# SONAR_UPDATEDSCH.net
KiCad netlist of a schematic drawn in EAGLE
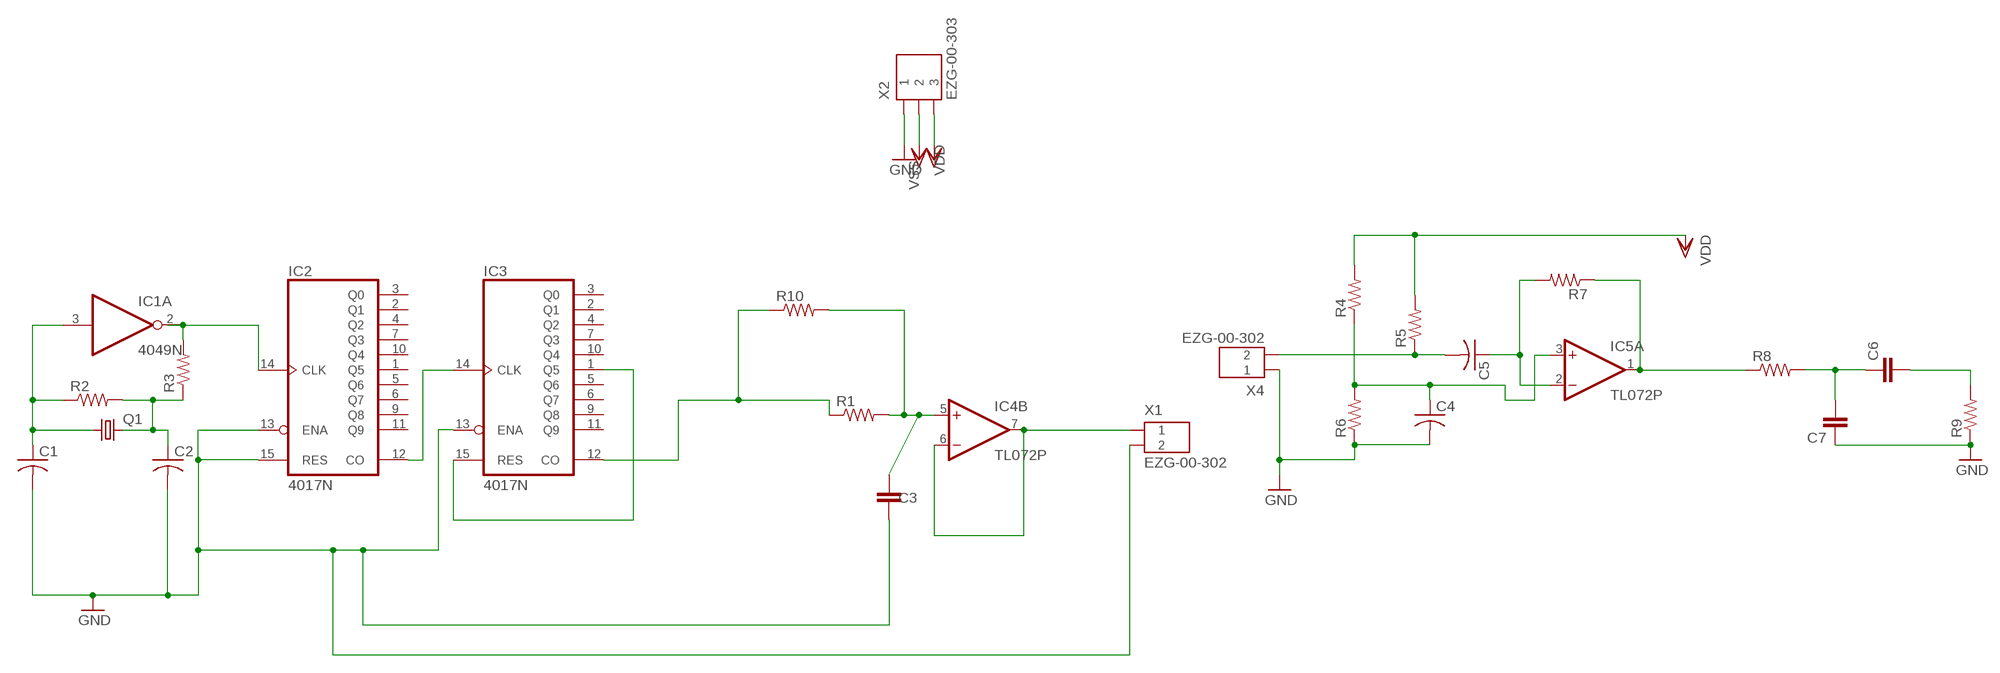
[diagram p0: schematic, sheet 1]

(export (version "E")
  (design (tool "Eeschema 10.0.6"))
  (components
    (comp (ref "C1")
      (value "C-US050-025X075")
      (footprint "eagle-import:C050-025X075")
      (libsource (lib "eagle-import") (part "C-US050-025X075"))
    )
    (comp (ref "C2")
      (value "C-US050-025X075")
      (footprint "eagle-import:C050-025X075")
      (libsource (lib "eagle-import") (part "C-US050-025X075"))
    )
    (comp (ref "C3")
      (value "C2.5/2")
      (footprint "eagle-import:C2.5-2")
      (libsource (lib "eagle-import") (part "C2.5/2"))
    )
    (comp (ref "C4")
      (value "C-US025-030X050")
      (footprint "eagle-import:C025-030X050")
      (libsource (lib "eagle-import") (part "C-US025-030X050"))
    )
    (comp (ref "C5")
      (value "C-US025-030X050")
      (footprint "eagle-import:C025-030X050")
      (libsource (lib "eagle-import") (part "C-US025-030X050"))
    )
    (comp (ref "C6")
      (value "C-EU025-030X050")
      (footprint "eagle-import:C025-030X050")
      (libsource (lib "eagle-import") (part "C-EU025-030X050"))
    )
    (comp (ref "C7")
      (value "C-EU025-030X050")
      (footprint "eagle-import:C025-030X050")
      (libsource (lib "eagle-import") (part "C-EU025-030X050"))
    )
    (comp (ref "IC1")
      (value "4049N")
      (footprint "eagle-import:DIL16")
      (libsource (lib "eagle-import") (part "4049N"))
    )
    (comp (ref "IC2")
      (value "4017N")
      (footprint "eagle-import:DIL16")
      (libsource (lib "eagle-import") (part "4017N"))
    )
    (comp (ref "IC3")
      (value "4017N")
      (footprint "eagle-import:DIL16")
      (libsource (lib "eagle-import") (part "4017N"))
    )
    (comp (ref "IC4")
      (value "TL072P")
      (footprint "eagle-import:DIL08")
      (libsource (lib "eagle-import") (part "TL072P"))
    )
    (comp (ref "IC5")
      (value "TL072P")
      (footprint "eagle-import:DIL08")
      (libsource (lib "eagle-import") (part "TL072P"))
    )
    (comp (ref "Q1")
      (value "CRYSTALHC49U-V")
      (footprint "eagle-import:HC49U-V")
      (libsource (lib "eagle-import") (part "CRYSTALHC49U-V"))
    )
    (comp (ref "R1")
      (value "R-US_0207/10")
      (footprint "eagle-import:0207_10")
      (libsource (lib "eagle-import") (part "R-US_0207/10"))
    )
    (comp (ref "R2")
      (value "R-US_0207/10")
      (footprint "eagle-import:0207_10")
      (libsource (lib "eagle-import") (part "R-US_0207/10"))
    )
    (comp (ref "R3")
      (value "R-US_0207/10")
      (footprint "eagle-import:0207_10")
      (libsource (lib "eagle-import") (part "R-US_0207/10"))
    )
    (comp (ref "R4")
      (value "R-US_0207/7")
      (footprint "eagle-import:0207_7")
      (libsource (lib "eagle-import") (part "R-US_0207/7"))
    )
    (comp (ref "R5")
      (value "R-US_0207/7")
      (footprint "eagle-import:0207_7")
      (libsource (lib "eagle-import") (part "R-US_0207/7"))
    )
    (comp (ref "R6")
      (value "R-US_0207/7")
      (footprint "eagle-import:0207_7")
      (libsource (lib "eagle-import") (part "R-US_0207/7"))
    )
    (comp (ref "R7")
      (value "R-US_0207/7")
      (footprint "eagle-import:0207_7")
      (libsource (lib "eagle-import") (part "R-US_0207/7"))
    )
    (comp (ref "R8")
      (value "R-US_0207/10")
      (footprint "eagle-import:0207_10")
      (libsource (lib "eagle-import") (part "R-US_0207/10"))
    )
    (comp (ref "R9")
      (value "R-US_0207/10")
      (footprint "eagle-import:0207_10")
      (libsource (lib "eagle-import") (part "R-US_0207/10"))
    )
    (comp (ref "R10")
      (value "R-US_0207/7")
      (footprint "eagle-import:0207_7")
      (libsource (lib "eagle-import") (part "R-US_0207/7"))
    )
    (comp (ref "X1")
      (value "EZG-00-302")
      (footprint "eagle-import:EZG-00-302")
      (libsource (lib "eagle-import") (part "EZG-?-30200"))
    )
    (comp (ref "X2")
      (value "EZG-00-303")
      (footprint "eagle-import:EZG-00-303")
      (libsource (lib "eagle-import") (part "EZG-?-30300"))
    )
    (comp (ref "X4")
      (value "EZG-00-302")
      (footprint "eagle-import:EZG-00-302")
      (libsource (lib "eagle-import") (part "EZG-?-30200"))
    )
  )
  (nets
    (net (code "1") (name "GND") (class "Default")
      (node (ref "C1") (pin "2") (pinfunction "2_2") (pintype "passive"))
      (node (ref "C2") (pin "2") (pinfunction "2_2") (pintype "passive"))
      (node (ref "C3") (pin "2") (pinfunction "2_2") (pintype "passive"))
      (node (ref "C4") (pin "2") (pinfunction "2_2") (pintype "passive"))
      (node (ref "C7") (pin "1") (pinfunction "1_1") (pintype "passive"))
      (node (ref "IC2") (pin "13") (pinfunction "ENA_13") (pintype "input"))
      (node (ref "IC2") (pin "15") (pinfunction "RES_15") (pintype "input"))
      (node (ref "IC3") (pin "13") (pinfunction "ENA_13") (pintype "input"))
      (node (ref "R6") (pin "1") (pinfunction "1_1") (pintype "passive"))
      (node (ref "R9") (pin "1") (pinfunction "1_1") (pintype "passive"))
      (node (ref "X1") (pin "2") (pinfunction "2_2") (pintype "passive"))
      (node (ref "X2") (pin "1") (pinfunction "1_1") (pintype "passive"))
      (node (ref "X4") (pin "1") (pinfunction "1_1") (pintype "passive"))
    )
    (net (code "2") (name "Net-(C2-Pad1)") (class "Default")
      (node (ref "C2") (pin "1") (pinfunction "1_1") (pintype "passive"))
      (node (ref "Q1") (pin "2") (pinfunction "2_2") (pintype "passive"))
      (node (ref "R2") (pin "2") (pinfunction "2_2") (pintype "passive"))
      (node (ref "R3") (pin "1") (pinfunction "1_1") (pintype "passive"))
    )
    (net (code "3") (name "Net-(C5-Pad2)") (class "Default")
      (node (ref "C5") (pin "2") (pinfunction "2_2") (pintype "passive"))
      (node (ref "R5") (pin "1") (pinfunction "1_1") (pintype "passive"))
      (node (ref "X4") (pin "2") (pinfunction "2_2") (pintype "passive"))
    )
    (net (code "4") (name "Net-(C6-Pad1)") (class "Default")
      (node (ref "C6") (pin "1") (pinfunction "1_1") (pintype "passive"))
      (node (ref "C7") (pin "2") (pinfunction "2_2") (pintype "passive"))
      (node (ref "R8") (pin "2") (pinfunction "2_2") (pintype "passive"))
    )
    (net (code "5") (name "Net-(C6-Pad2)") (class "Default")
      (node (ref "C6") (pin "2") (pinfunction "2_2") (pintype "passive"))
      (node (ref "R9") (pin "2") (pinfunction "2_2") (pintype "passive"))
    )
    (net (code "6") (name "Net-(IC1A-I)") (class "Default")
      (node (ref "C1") (pin "1") (pinfunction "1_1") (pintype "passive"))
      (node (ref "IC1") (pin "3") (pinfunction "I_3") (pintype "input"))
      (node (ref "Q1") (pin "1") (pinfunction "1_1") (pintype "passive"))
      (node (ref "R2") (pin "1") (pinfunction "1_1") (pintype "passive"))
    )
    (net (code "7") (name "Net-(IC1A-O)") (class "Default")
      (node (ref "IC1") (pin "2") (pinfunction "O_2") (pintype "output"))
      (node (ref "IC2") (pin "14") (pinfunction "CLK_14") (pintype "input"))
      (node (ref "R3") (pin "2") (pinfunction "2_2") (pintype "passive"))
    )
    (net (code "8") (name "Net-(IC2A-CO)") (class "Default")
      (node (ref "IC2") (pin "12") (pinfunction "CO_12") (pintype "output"))
      (node (ref "IC3") (pin "14") (pinfunction "CLK_14") (pintype "input"))
    )
    (net (code "9") (name "Net-(IC3A-CO)") (class "Default")
      (node (ref "IC3") (pin "12") (pinfunction "CO_12") (pintype "output"))
      (node (ref "R1") (pin "1") (pinfunction "1_1") (pintype "passive"))
      (node (ref "R10") (pin "1") (pinfunction "1_1") (pintype "passive"))
    )
    (net (code "10") (name "Net-(IC3A-Q5)") (class "Default")
      (node (ref "IC3") (pin "1") (pinfunction "Q5_1") (pintype "output"))
      (node (ref "IC3") (pin "15") (pinfunction "RES_15") (pintype "input"))
    )
    (net (code "11") (name "Net-(IC4B-+IN)") (class "Default")
      (node (ref "C3") (pin "1") (pinfunction "1_1") (pintype "passive"))
      (node (ref "IC4") (pin "5") (pinfunction "+IN_5") (pintype "input"))
      (node (ref "R1") (pin "2") (pinfunction "2_2") (pintype "passive"))
      (node (ref "R10") (pin "2") (pinfunction "2_2") (pintype "passive"))
    )
    (net (code "12") (name "Net-(IC4B--IN)") (class "Default")
      (node (ref "IC4") (pin "6") (pinfunction "-IN_6") (pintype "input"))
      (node (ref "IC4") (pin "7") (pinfunction "OUT_7") (pintype "output"))
      (node (ref "X1") (pin "1") (pinfunction "1_1") (pintype "passive"))
    )
    (net (code "13") (name "Net-(IC5A-+IN)") (class "Default")
      (node (ref "C4") (pin "1") (pinfunction "1_1") (pintype "passive"))
      (node (ref "IC5") (pin "3") (pinfunction "+IN_3") (pintype "input"))
      (node (ref "R4") (pin "1") (pinfunction "1_1") (pintype "passive"))
      (node (ref "R6") (pin "2") (pinfunction "2_2") (pintype "passive"))
    )
    (net (code "14") (name "Net-(IC5A--IN)") (class "Default")
      (node (ref "C5") (pin "1") (pinfunction "1_1") (pintype "passive"))
      (node (ref "IC5") (pin "2") (pinfunction "-IN_2") (pintype "input"))
      (node (ref "R7") (pin "2") (pinfunction "2_2") (pintype "passive"))
    )
    (net (code "15") (name "Net-(IC5A-OUT)") (class "Default")
      (node (ref "IC5") (pin "1") (pinfunction "OUT_1") (pintype "output"))
      (node (ref "R7") (pin "1") (pinfunction "1_1") (pintype "passive"))
      (node (ref "R8") (pin "1") (pinfunction "1_1") (pintype "passive"))
    )
    (net (code "16") (name "VDD") (class "Default")
      (node (ref "R4") (pin "2") (pinfunction "2_2") (pintype "passive"))
      (node (ref "R5") (pin "2") (pinfunction "2_2") (pintype "passive"))
      (node (ref "X2") (pin "2") (pinfunction "2_2") (pintype "passive"))
    )
    (net (code "17") (name "VSS") (class "Default")
      (node (ref "X2") (pin "3") (pinfunction "3_3") (pintype "passive"))
    )
    (net (code "18") (name "unconnected-(IC2A-Q0-Pad3)") (class "Default")
      (node (ref "IC2") (pin "3") (pinfunction "Q0_3") (pintype "output"))
    )
    (net (code "19") (name "unconnected-(IC2A-Q1-Pad2)") (class "Default")
      (node (ref "IC2") (pin "2") (pinfunction "Q1_2") (pintype "output"))
    )
    (net (code "20") (name "unconnected-(IC2A-Q2-Pad4)") (class "Default")
      (node (ref "IC2") (pin "4") (pinfunction "Q2_4") (pintype "output"))
    )
    (net (code "21") (name "unconnected-(IC2A-Q3-Pad7)") (class "Default")
      (node (ref "IC2") (pin "7") (pinfunction "Q3_7") (pintype "output"))
    )
    (net (code "22") (name "unconnected-(IC2A-Q4-Pad10)") (class "Default")
      (node (ref "IC2") (pin "10") (pinfunction "Q4_10") (pintype "output"))
    )
    (net (code "23") (name "unconnected-(IC2A-Q5-Pad1)") (class "Default")
      (node (ref "IC2") (pin "1") (pinfunction "Q5_1") (pintype "output"))
    )
    (net (code "24") (name "unconnected-(IC2A-Q6-Pad5)") (class "Default")
      (node (ref "IC2") (pin "5") (pinfunction "Q6_5") (pintype "output"))
    )
    (net (code "25") (name "unconnected-(IC2A-Q7-Pad6)") (class "Default")
      (node (ref "IC2") (pin "6") (pinfunction "Q7_6") (pintype "output"))
    )
    (net (code "26") (name "unconnected-(IC2A-Q8-Pad9)") (class "Default")
      (node (ref "IC2") (pin "9") (pinfunction "Q8_9") (pintype "output"))
    )
    (net (code "27") (name "unconnected-(IC2A-Q9-Pad11)") (class "Default")
      (node (ref "IC2") (pin "11") (pinfunction "Q9_11") (pintype "output"))
    )
    (net (code "28") (name "unconnected-(IC3A-Q0-Pad3)") (class "Default")
      (node (ref "IC3") (pin "3") (pinfunction "Q0_3") (pintype "output"))
    )
    (net (code "29") (name "unconnected-(IC3A-Q1-Pad2)") (class "Default")
      (node (ref "IC3") (pin "2") (pinfunction "Q1_2") (pintype "output"))
    )
    (net (code "30") (name "unconnected-(IC3A-Q2-Pad4)") (class "Default")
      (node (ref "IC3") (pin "4") (pinfunction "Q2_4") (pintype "output"))
    )
    (net (code "31") (name "unconnected-(IC3A-Q3-Pad7)") (class "Default")
      (node (ref "IC3") (pin "7") (pinfunction "Q3_7") (pintype "output"))
    )
    (net (code "32") (name "unconnected-(IC3A-Q4-Pad10)") (class "Default")
      (node (ref "IC3") (pin "10") (pinfunction "Q4_10") (pintype "output"))
    )
    (net (code "33") (name "unconnected-(IC3A-Q6-Pad5)") (class "Default")
      (node (ref "IC3") (pin "5") (pinfunction "Q6_5") (pintype "output"))
    )
    (net (code "34") (name "unconnected-(IC3A-Q7-Pad6)") (class "Default")
      (node (ref "IC3") (pin "6") (pinfunction "Q7_6") (pintype "output"))
    )
    (net (code "35") (name "unconnected-(IC3A-Q8-Pad9)") (class "Default")
      (node (ref "IC3") (pin "9") (pinfunction "Q8_9") (pintype "output"))
    )
    (net (code "36") (name "unconnected-(IC3A-Q9-Pad11)") (class "Default")
      (node (ref "IC3") (pin "11") (pinfunction "Q9_11") (pintype "output"))
    )
  )
)
